# small_mavric.net
KiCad netlist of a schematic drawn in EAGLE
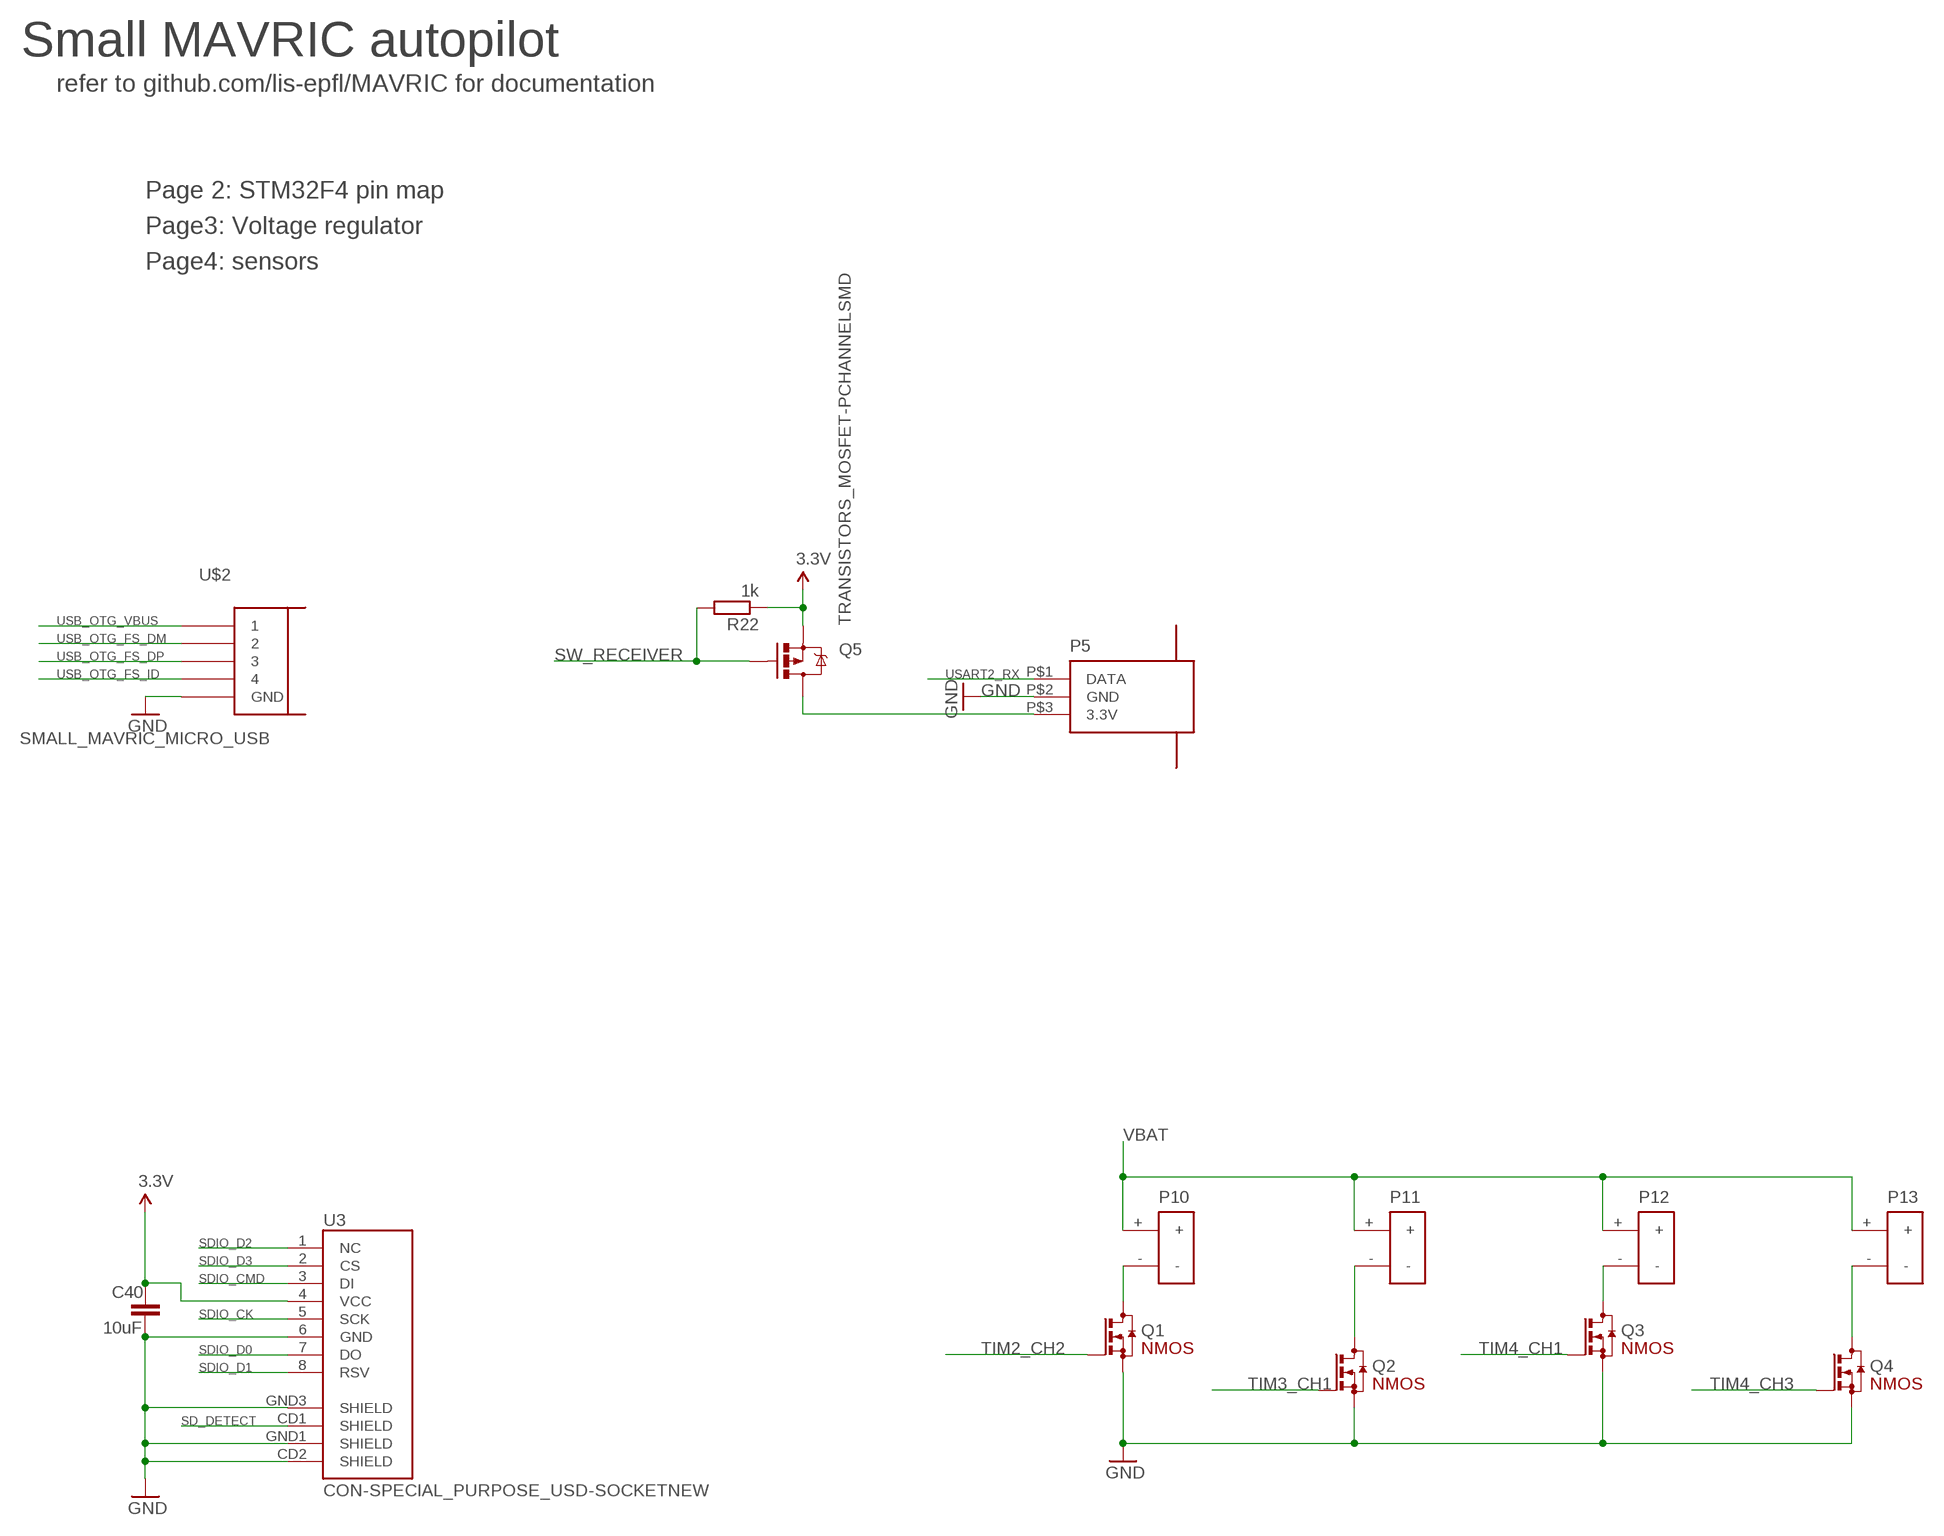
[diagram p0: schematic, sheet 1]
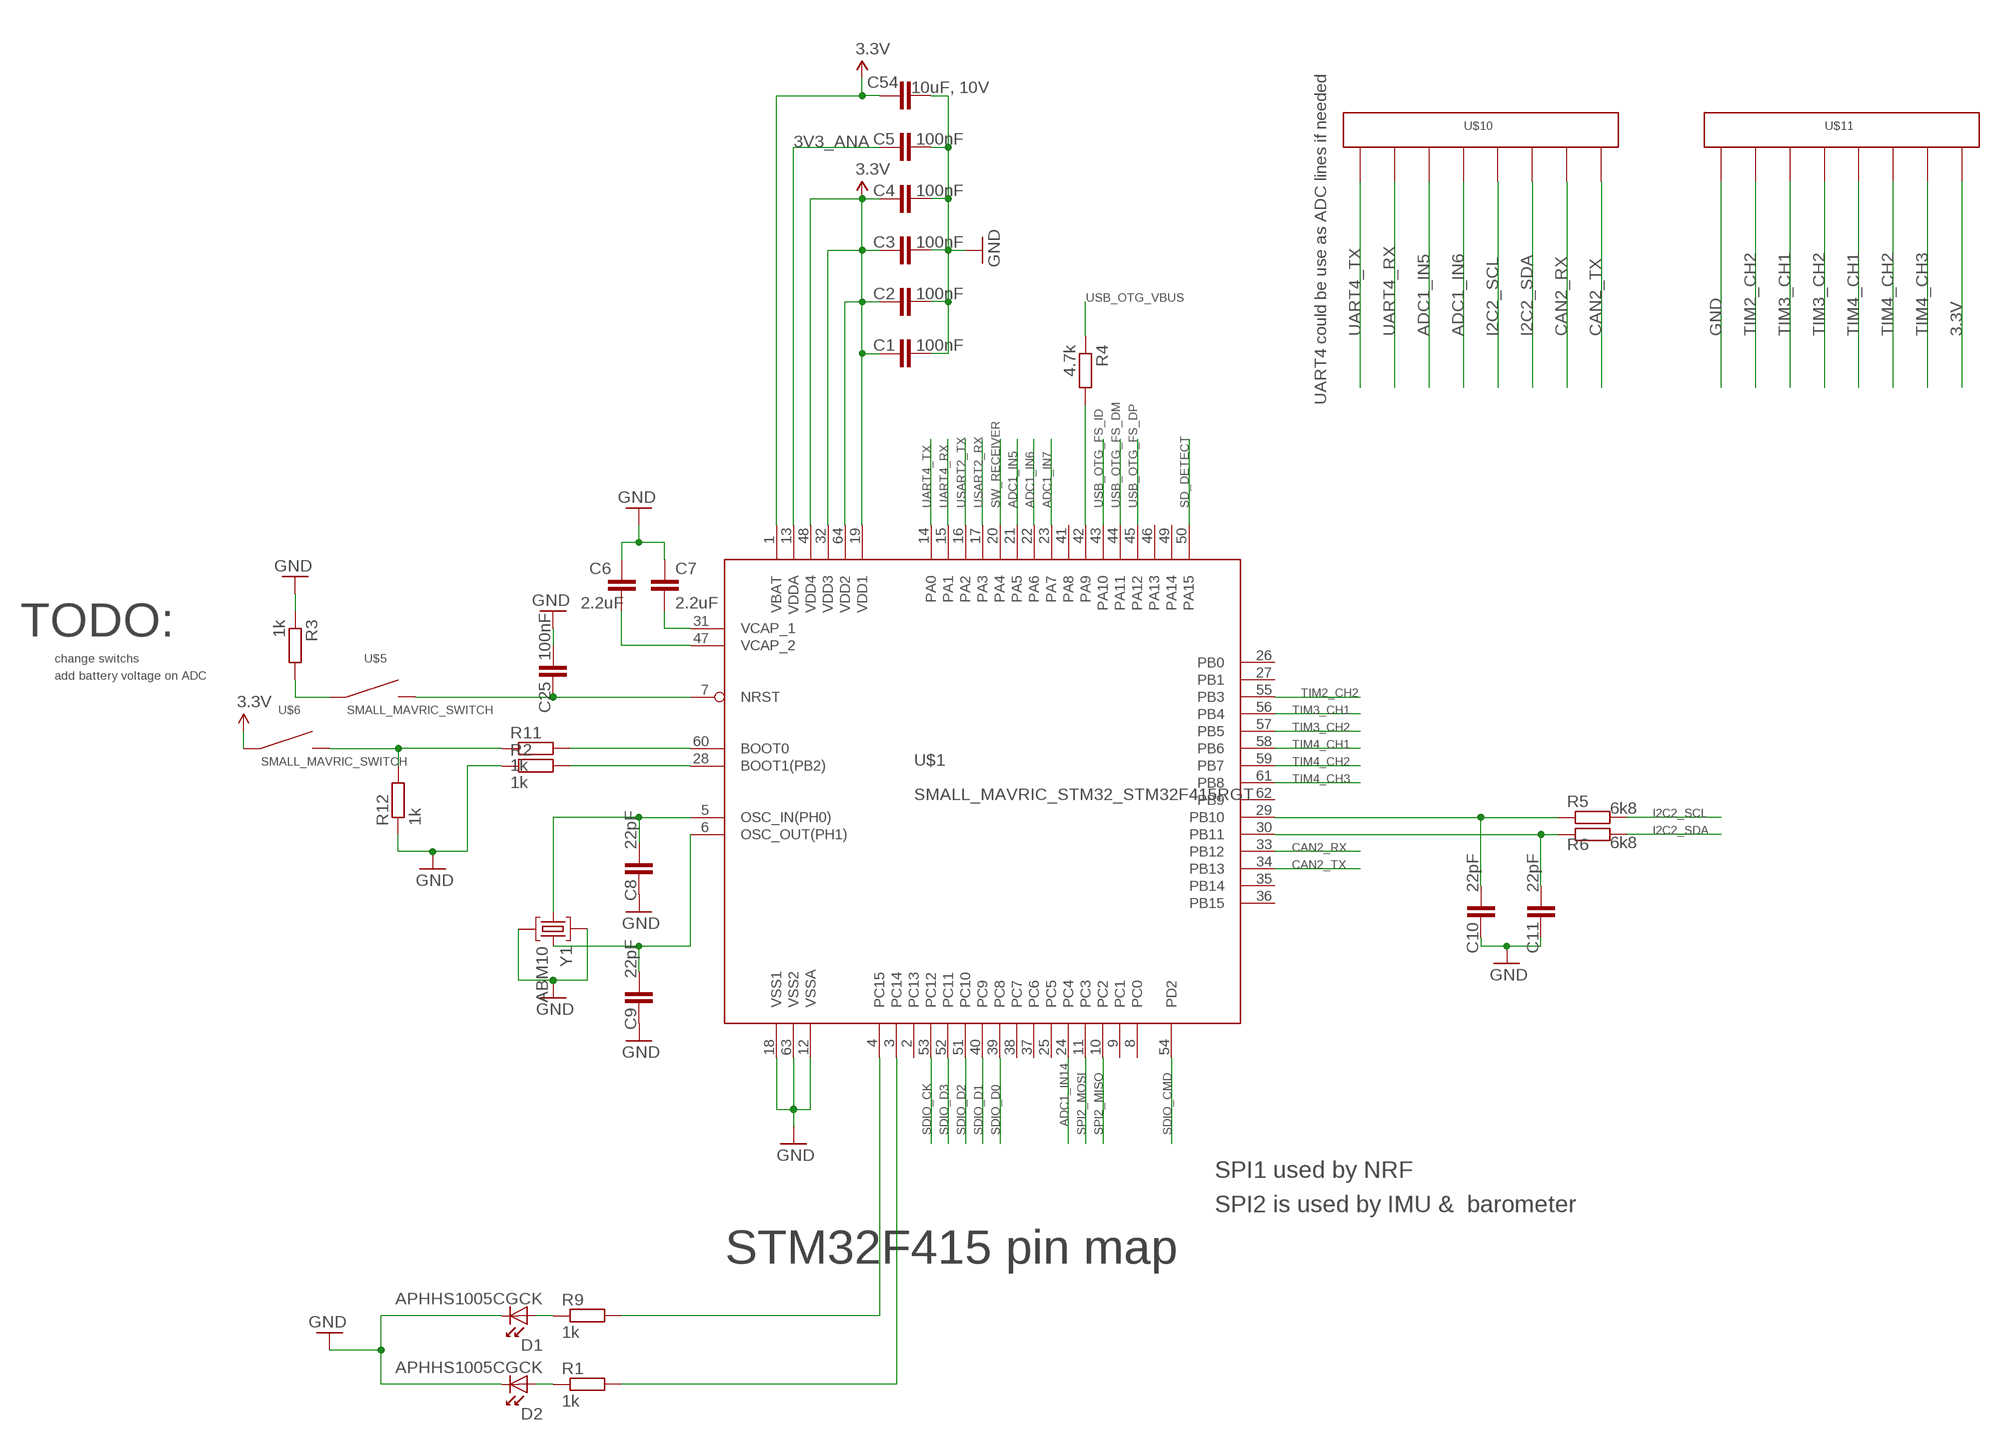
[diagram p1: schematic, sheet 2]
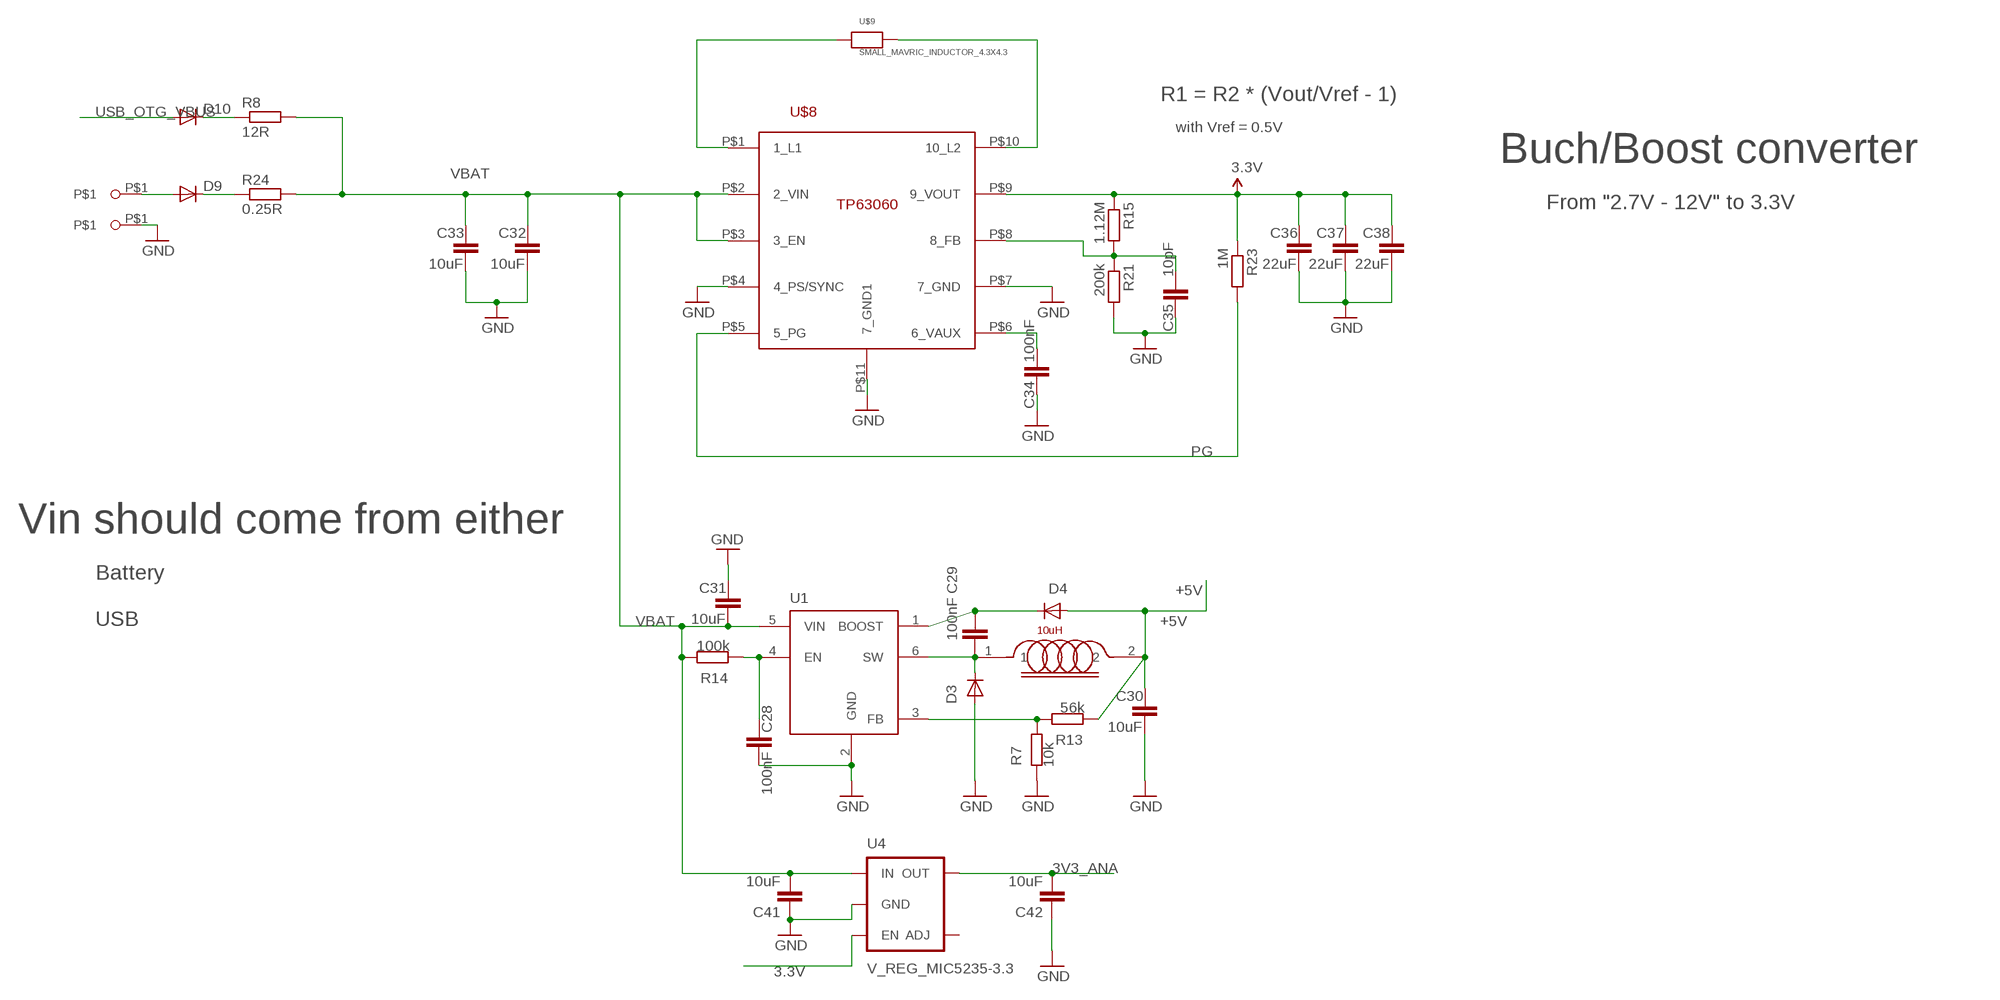
[diagram p2: schematic, sheet 3]
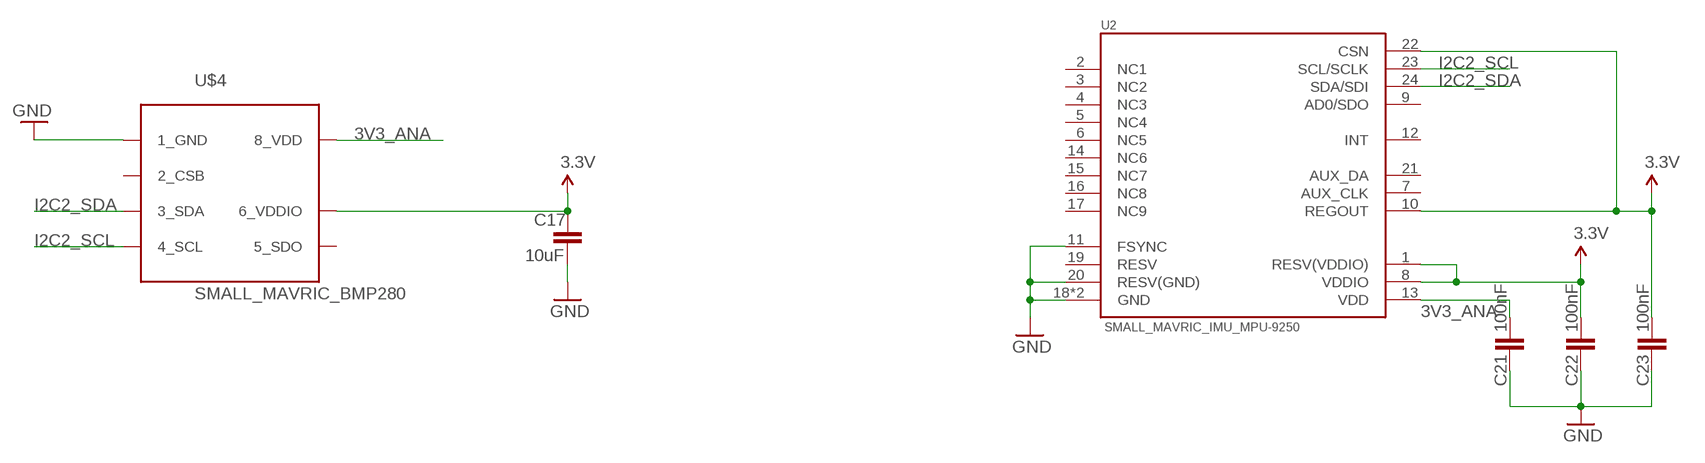
[diagram p3: schematic, sheet 4]

(export (version "E")
  (design (tool "Eeschema 10.0.6"))
  (components
    (comp (ref "C40")
      (value "10uF")
      (footprint "eagle-import:SMALL_MAVRIC_SMALL_MAVRIC_CAPACITOR_C0603")
      (fields (field (name "PLACE_PART") "YES") (field (name "PARTNO") "2.2UF 16V 0603"))
      (libsource (lib "eagle-import") (part "SMALL_MAVRIC_CAPACITOR_C0603"))
    )
    (comp (ref "P5")
      (value "CON-SPECIAL_PURPOSE_SPEKTRUM_RECEIVER")
      (footprint "eagle-import:CON-SPECIAL_PURPOSE_JST_1.5MM_3WAY")
      (fields (field (name "PLACE_PART") "YES"))
      (libsource (lib "eagle-import") (part "CON-SPECIAL_PURPOSE_SPEKTRUM_RECEIVER"))
    )
    (comp (ref "P10")
      (value "POWERSMALL_SMD")
      (footprint "eagle-import:POWER_SMALL_SMD")
      (fields (field (name "PLACE_PART") "NO"))
      (libsource (lib "eagle-import") (part "POWERSMALL_SMD"))
    )
    (comp (ref "P11")
      (value "POWERSMALL_SMD")
      (footprint "eagle-import:POWER_SMALL_SMD")
      (fields (field (name "PLACE_PART") "NO"))
      (libsource (lib "eagle-import") (part "POWERSMALL_SMD"))
    )
    (comp (ref "P12")
      (value "POWERSMALL_SMD")
      (footprint "eagle-import:POWER_SMALL_SMD")
      (fields (field (name "PLACE_PART") "NO"))
      (libsource (lib "eagle-import") (part "POWERSMALL_SMD"))
    )
    (comp (ref "P13")
      (value "POWERSMALL_SMD")
      (footprint "eagle-import:POWER_SMALL_SMD")
      (fields (field (name "PLACE_PART") "NO"))
      (libsource (lib "eagle-import") (part "POWERSMALL_SMD"))
    )
    (comp (ref "Q1")
      (value "N-CHANNEL_SOT23")
      (footprint "eagle-import:SOT23")
      (fields (field (name "PLACE_PART") "YES"))
      (libsource (lib "eagle-import") (part "N-CHANNEL_SOT23"))
    )
    (comp (ref "Q2")
      (value "N-CHANNEL_SOT23")
      (footprint "eagle-import:SOT23")
      (fields (field (name "PLACE_PART") "YES"))
      (libsource (lib "eagle-import") (part "N-CHANNEL_SOT23"))
    )
    (comp (ref "Q3")
      (value "N-CHANNEL_SOT23")
      (footprint "eagle-import:SOT23")
      (fields (field (name "PLACE_PART") "YES"))
      (libsource (lib "eagle-import") (part "N-CHANNEL_SOT23"))
    )
    (comp (ref "Q4")
      (value "N-CHANNEL_SOT23")
      (footprint "eagle-import:SOT23")
      (fields (field (name "PLACE_PART") "YES"))
      (libsource (lib "eagle-import") (part "N-CHANNEL_SOT23"))
    )
    (comp (ref "Q5")
      (value "TRANSISTORS_MOSFET-PCHANNELSMD")
      (footprint "eagle-import:TRANSISTORS_SOT23-3")
      (fields (field (name "PLACE_PART") "YES") (field (name "PLACE_PART_1") "YES"))
      (libsource (lib "eagle-import") (part "TRANSISTORS_MOSFET-PCHANNELSMD"))
    )
    (comp (ref "R22")
      (value "1k")
      (footprint "eagle-import:SMALL_MAVRIC_SMALL_MAVRIC_RESISTOR_R0402")
      (fields (field (name "PLACE_PART") "YES") (field (name "PLACE_PART_1") "YES"))
      (libsource (lib "eagle-import") (part "SMALL_MAVRIC_RESISTOR_R0402"))
    )
    (comp (ref "U$2")
      (value "SMALL_MAVRIC_MICRO_USB")
      (footprint "eagle-import:SMALL_MAVRIC_MICR0_USB")
      (fields (field (name "PLACE_PART") "YES") (field (name "ORDER_CODE") "538-47589-0001"))
      (libsource (lib "eagle-import") (part "SMALL_MAVRIC_MICRO_USB"))
    )
    (comp (ref "U3")
      (value "CON-SPECIAL_PURPOSE_USD-SOCKETNEW")
      (footprint "eagle-import:CON-SPECIAL_PURPOSE_MICRO-SD-SOCKET-PP")
      (fields (field (name "PLACE_PART") "YES"))
      (libsource (lib "eagle-import") (part "CON-SPECIAL_PURPOSE_USD-SOCKETNEW"))
    )
    (comp (ref "C28")
      (value "100nF")
      (footprint "eagle-import:SMALL_MAVRIC_SMALL_MAVRIC_CAPACITOR_C0402")
      (fields (field (name "PLACE_PART") "YES"))
      (libsource (lib "eagle-import") (part "SMALL_MAVRIC_CAPACITOR_C0402"))
    )
    (comp (ref "C29")
      (value "100nF")
      (footprint "eagle-import:SMALL_MAVRIC_SMALL_MAVRIC_CAPACITOR_C0402")
      (fields (field (name "PLACE_PART") "YES"))
      (libsource (lib "eagle-import") (part "SMALL_MAVRIC_CAPACITOR_C0402"))
    )
    (comp (ref "C30")
      (value "10uF")
      (footprint "eagle-import:SMALL_MAVRIC_SMALL_MAVRIC_CAPACITOR_C0603")
      (fields (field (name "PLACE_PART") "YES") (field (name "PARTNO") "2.2UF 16V 0603"))
      (libsource (lib "eagle-import") (part "SMALL_MAVRIC_CAPACITOR_C0603"))
    )
    (comp (ref "C31")
      (value "10uF")
      (footprint "eagle-import:SMALL_MAVRIC_SMALL_MAVRIC_CAPACITOR_C0603")
      (fields (field (name "PLACE_PART") "YES") (field (name "PARTNO") "2.2UF 16V 0603"))
      (libsource (lib "eagle-import") (part "SMALL_MAVRIC_CAPACITOR_C0603"))
    )
    (comp (ref "C32")
      (value "10uF")
      (footprint "eagle-import:SMALL_MAVRIC_SMALL_MAVRIC_CAPACITOR_C0603")
      (fields (field (name "PLACE_PART") "YES") (field (name "PARTNO") "2.2UF 16V 0603"))
      (libsource (lib "eagle-import") (part "SMALL_MAVRIC_CAPACITOR_C0603"))
    )
    (comp (ref "C33")
      (value "10uF")
      (footprint "eagle-import:SMALL_MAVRIC_SMALL_MAVRIC_CAPACITOR_C0603")
      (fields (field (name "PLACE_PART") "YES") (field (name "PARTNO") "2.2UF 16V 0603"))
      (libsource (lib "eagle-import") (part "SMALL_MAVRIC_CAPACITOR_C0603"))
    )
    (comp (ref "C34")
      (value "100nF")
      (footprint "eagle-import:SMALL_MAVRIC_SMALL_MAVRIC_CAPACITOR_C0402")
      (fields (field (name "PLACE_PART") "YES"))
      (libsource (lib "eagle-import") (part "SMALL_MAVRIC_CAPACITOR_C0402"))
    )
    (comp (ref "C35")
      (value "10pF")
      (footprint "eagle-import:SMALL_MAVRIC_SMALL_MAVRIC_CAPACITOR_C0402")
      (fields (field (name "PLACE_PART") "YES"))
      (libsource (lib "eagle-import") (part "SMALL_MAVRIC_CAPACITOR_C0402"))
    )
    (comp (ref "C36")
      (value "22uF")
      (footprint "eagle-import:SMALL_MAVRIC_SMALL_MAVRIC_CAPACITOR_C0603")
      (fields (field (name "PLACE_PART") "YES") (field (name "PARTNO") "2.2UF 16V 0603"))
      (libsource (lib "eagle-import") (part "SMALL_MAVRIC_CAPACITOR_C0603"))
    )
    (comp (ref "C37")
      (value "22uF")
      (footprint "eagle-import:SMALL_MAVRIC_SMALL_MAVRIC_CAPACITOR_C0603")
      (fields (field (name "PLACE_PART") "YES") (field (name "PARTNO") "2.2UF 16V 0603"))
      (libsource (lib "eagle-import") (part "SMALL_MAVRIC_CAPACITOR_C0603"))
    )
    (comp (ref "C38")
      (value "22uF")
      (footprint "eagle-import:SMALL_MAVRIC_SMALL_MAVRIC_CAPACITOR_C0603")
      (fields (field (name "PLACE_PART") "YES") (field (name "PARTNO") "2.2UF 16V 0603"))
      (libsource (lib "eagle-import") (part "SMALL_MAVRIC_CAPACITOR_C0603"))
    )
    (comp (ref "C41")
      (value "10uF")
      (footprint "eagle-import:C0805")
      (fields (field (name "PLACE_PART") "YES"))
      (libsource (lib "eagle-import") (part "C-EUC0805"))
    )
    (comp (ref "C42")
      (value "10uF")
      (footprint "eagle-import:C0805")
      (fields (field (name "PLACE_PART") "YES"))
      (libsource (lib "eagle-import") (part "C-EUC0805"))
    )
    (comp (ref "D3")
      (value "SMALL_MAVRIC_POWER_DIODESOD")
      (footprint "eagle-import:SMALL_MAVRIC_POWER_SOD-323")
      (fields
        (field (name "PLACE_PART") "YES")
        (field (name "DISTRIBUTOR") "Digikey")
        (field (name "ORDER_CODE") "568-4128-1-ND")
      )
      (libsource (lib "eagle-import") (part "SMALL_MAVRIC_POWER_DIODESOD"))
    )
    (comp (ref "D4")
      (value "SMALL_MAVRIC_POWER_DIODESOD")
      (footprint "eagle-import:SMALL_MAVRIC_POWER_SOD-323")
      (fields
        (field (name "PLACE_PART") "YES")
        (field (name "DISTRIBUTOR") "Digikey")
        (field (name "ORDER_CODE") "568-4128-1-ND")
      )
      (libsource (lib "eagle-import") (part "SMALL_MAVRIC_POWER_DIODESOD"))
    )
    (comp (ref "D9")
      (value "SMALL_MAVRIC_POWER_DIODESOD")
      (footprint "eagle-import:SMALL_MAVRIC_POWER_SOD-323")
      (fields
        (field (name "PLACE_PART") "YES")
        (field (name "DISTRIBUTOR") "Digikey")
        (field (name "ORDER_CODE") "568-4128-1-ND")
      )
      (libsource (lib "eagle-import") (part "SMALL_MAVRIC_POWER_DIODESOD"))
    )
    (comp (ref "D10")
      (value "SMALL_MAVRIC_POWER_DIODESOD")
      (footprint "eagle-import:SMALL_MAVRIC_POWER_SOD-323")
      (fields
        (field (name "PLACE_PART") "YES")
        (field (name "DISTRIBUTOR") "Digikey")
        (field (name "ORDER_CODE") "568-4128-1-ND")
        (field (name "PLACE_PART_1") "YES")
      )
      (libsource (lib "eagle-import") (part "SMALL_MAVRIC_POWER_DIODESOD"))
    )
    (comp (ref "L1")
      (value "10uH")
      (footprint "eagle-import:POWER_C1210")
      (fields (field (name "PLACE_PART") "YES"))
      (libsource (lib "eagle-import") (part "POWER_INDUCTOR1210"))
    )
    (comp (ref "R7")
      (value "10k")
      (footprint "eagle-import:SMALL_MAVRIC_SMALL_MAVRIC_RESISTOR_R0402")
      (fields (field (name "PLACE_PART") "YES"))
      (libsource (lib "eagle-import") (part "SMALL_MAVRIC_RESISTOR_R0402"))
    )
    (comp (ref "R8")
      (value "12R")
      (footprint "eagle-import:SMALL_MAVRIC_SMALL_MAVRIC_RESISTOR_R0402")
      (fields (field (name "PLACE_PART") "YES"))
      (libsource (lib "eagle-import") (part "SMALL_MAVRIC_RESISTOR_R0402"))
    )
    (comp (ref "R13")
      (value "56k")
      (footprint "eagle-import:SMALL_MAVRIC_SMALL_MAVRIC_RESISTOR_R0402")
      (fields (field (name "PLACE_PART") "YES"))
      (libsource (lib "eagle-import") (part "SMALL_MAVRIC_RESISTOR_R0402"))
    )
    (comp (ref "R14")
      (value "100k")
      (footprint "eagle-import:SMALL_MAVRIC_SMALL_MAVRIC_RESISTOR_R0402")
      (fields (field (name "PLACE_PART") "YES"))
      (libsource (lib "eagle-import") (part "SMALL_MAVRIC_RESISTOR_R0402"))
    )
    (comp (ref "R15")
      (value "1.12M")
      (footprint "eagle-import:SMALL_MAVRIC_SMALL_MAVRIC_RESISTOR_R0402")
      (fields (field (name "PLACE_PART") "YES"))
      (libsource (lib "eagle-import") (part "SMALL_MAVRIC_RESISTOR_R0402"))
    )
    (comp (ref "R21")
      (value "200k")
      (footprint "eagle-import:SMALL_MAVRIC_SMALL_MAVRIC_RESISTOR_R0402")
      (fields (field (name "PLACE_PART") "YES"))
      (libsource (lib "eagle-import") (part "SMALL_MAVRIC_RESISTOR_R0402"))
    )
    (comp (ref "R23")
      (value "1M")
      (footprint "eagle-import:SMALL_MAVRIC_SMALL_MAVRIC_RESISTOR_R0402")
      (fields (field (name "PLACE_PART") "YES"))
      (libsource (lib "eagle-import") (part "SMALL_MAVRIC_RESISTOR_R0402"))
    )
    (comp (ref "R24")
      (value "0.25R")
      (footprint "eagle-import:SMALL_MAVRIC_SMALL_MAVRIC_RESISTOR_R0402")
      (fields (field (name "PLACE_PART") "YES"))
      (libsource (lib "eagle-import") (part "SMALL_MAVRIC_RESISTOR_R0402"))
    )
    (comp (ref "U$8")
      (value "SMALL_MAVRIC_POWER_TPS63060")
      (footprint "eagle-import:SMALL_MAVRIC_POWER_PWSON")
      (fields (field (name "PLACE_PART") "YES"))
      (libsource (lib "eagle-import") (part "SMALL_MAVRIC_POWER_TPS63060"))
    )
    (comp (ref "U$9")
      (value "SMALL_MAVRIC_INDUCTOR_4.3X4.3")
      (footprint "eagle-import:SMALL_MAVRIC_SMALL_MAVRIC_SMALL_MAVRIC_INDUCTOR_4.3X4.3")
      (fields
        (field (name "PLACE_PART") "YES")
        (field (name "DISTRIBUTOR") "mouser")
        (field (name "ORDER_CODE") "994-XFL4020-102MEC")
      )
      (libsource (lib "eagle-import") (part "SMALL_MAVRIC_INDUCTOR_4.3X4.3"))
    )
    (comp (ref "U$15")
      (value "SMALL_MAVRIC_SMALL_CONNECTOR")
      (footprint "eagle-import:SMALL_MAVRIC_SMALL_CONN")
      (fields
        (field (name "PLACE_PART") "YES")
        (field (name "DISTRIBUTOR") "Mouser")
        (field (name "PLACE_PART_1") "YES")
      )
      (libsource (lib "eagle-import") (part "SMALL_MAVRIC_SMALL_CONNECTOR"))
    )
    (comp (ref "U$16")
      (value "SMALL_MAVRIC_SMALL_CONNECTOR")
      (footprint "eagle-import:SMALL_MAVRIC_SMALL_CONN")
      (fields
        (field (name "PLACE_PART") "YES")
        (field (name "DISTRIBUTOR") "Mouser")
        (field (name "PLACE_PART_1") "YES")
      )
      (libsource (lib "eagle-import") (part "SMALL_MAVRIC_SMALL_CONNECTOR"))
    )
    (comp (ref "U1")
      (value "POWER_LM2734")
      (footprint "eagle-import:POWER_SOT23-6")
      (fields (field (name "PLACE_PART") "YES"))
      (libsource (lib "eagle-import") (part "POWER_LM2734"))
    )
    (comp (ref "U4")
      (value "V_REG_MIC5235-3.3")
      (footprint "eagle-import:SOT23-5")
      (fields (field (name "PLACE_PART") "YES"))
      (libsource (lib "eagle-import") (part "V_REG_MIC5235"))
    )
    (comp (ref "C1")
      (value "100nF")
      (footprint "eagle-import:SMALL_MAVRIC_SMALL_MAVRIC_CAPACITOR_C0402")
      (fields (field (name "PLACE_PART") "YES"))
      (libsource (lib "eagle-import") (part "SMALL_MAVRIC_CAPACITOR_C0402"))
    )
    (comp (ref "C2")
      (value "100nF")
      (footprint "eagle-import:SMALL_MAVRIC_SMALL_MAVRIC_CAPACITOR_C0402")
      (fields (field (name "PLACE_PART") "YES"))
      (libsource (lib "eagle-import") (part "SMALL_MAVRIC_CAPACITOR_C0402"))
    )
    (comp (ref "C3")
      (value "100nF")
      (footprint "eagle-import:SMALL_MAVRIC_SMALL_MAVRIC_CAPACITOR_C0402")
      (fields (field (name "PLACE_PART") "YES"))
      (libsource (lib "eagle-import") (part "SMALL_MAVRIC_CAPACITOR_C0402"))
    )
    (comp (ref "C4")
      (value "100nF")
      (footprint "eagle-import:SMALL_MAVRIC_SMALL_MAVRIC_CAPACITOR_C0402")
      (fields (field (name "PLACE_PART") "YES"))
      (libsource (lib "eagle-import") (part "SMALL_MAVRIC_CAPACITOR_C0402"))
    )
    (comp (ref "C5")
      (value "100nF")
      (footprint "eagle-import:SMALL_MAVRIC_SMALL_MAVRIC_CAPACITOR_C0402")
      (fields (field (name "PLACE_PART") "YES"))
      (libsource (lib "eagle-import") (part "SMALL_MAVRIC_CAPACITOR_C0402"))
    )
    (comp (ref "C6")
      (value "2.2uF")
      (footprint "eagle-import:SMALL_MAVRIC_SMALL_MAVRIC_CAPACITOR_C0603")
      (fields (field (name "PLACE_PART") "YES") (field (name "PARTNO") "2.2UF 16V 0603"))
      (libsource (lib "eagle-import") (part "SMALL_MAVRIC_CAPACITOR_C0603"))
    )
    (comp (ref "C7")
      (value "2.2uF")
      (footprint "eagle-import:SMALL_MAVRIC_SMALL_MAVRIC_CAPACITOR_C0603")
      (fields (field (name "PLACE_PART") "YES") (field (name "PARTNO") "2.2UF 16V 0603"))
      (libsource (lib "eagle-import") (part "SMALL_MAVRIC_CAPACITOR_C0603"))
    )
    (comp (ref "C8")
      (value "22pF")
      (footprint "eagle-import:SMALL_MAVRIC_SMALL_MAVRIC_CAPACITOR_C0402")
      (fields (field (name "PLACE_PART") "YES"))
      (libsource (lib "eagle-import") (part "SMALL_MAVRIC_CAPACITOR_C0402"))
    )
    (comp (ref "C9")
      (value "22pF")
      (footprint "eagle-import:SMALL_MAVRIC_SMALL_MAVRIC_CAPACITOR_C0402")
      (fields (field (name "PLACE_PART") "YES"))
      (libsource (lib "eagle-import") (part "SMALL_MAVRIC_CAPACITOR_C0402"))
    )
    (comp (ref "C10")
      (value "22pF")
      (footprint "eagle-import:SMALL_MAVRIC_SMALL_MAVRIC_CAPACITOR_C0402")
      (fields (field (name "PLACE_PART") "YES"))
      (libsource (lib "eagle-import") (part "SMALL_MAVRIC_CAPACITOR_C0402"))
    )
    (comp (ref "C11")
      (value "22pF")
      (footprint "eagle-import:SMALL_MAVRIC_SMALL_MAVRIC_CAPACITOR_C0402")
      (fields (field (name "PLACE_PART") "YES"))
      (libsource (lib "eagle-import") (part "SMALL_MAVRIC_CAPACITOR_C0402"))
    )
    (comp (ref "C25")
      (value "100nF")
      (footprint "eagle-import:SMALL_MAVRIC_SMALL_MAVRIC_CAPACITOR_C0402")
      (fields (field (name "PLACE_PART") "YES"))
      (libsource (lib "eagle-import") (part "SMALL_MAVRIC_CAPACITOR_C0402"))
    )
    (comp (ref "C54")
      (value "10uF, 10V")
      (footprint "eagle-import:SMALL_MAVRIC_SMALL_MAVRIC_CAPACITOR_C0603")
      (fields (field (name "PLACE_PART") "YES") (field (name "PARTNO") "10UF 10V 0805"))
      (libsource (lib "eagle-import") (part "SMALL_MAVRIC_CAPACITOR_C0603"))
    )
    (comp (ref "D1")
      (value "APHHS1005CGCK")
      (footprint "eagle-import:LED_0402")
      (libsource (lib "eagle-import") (part "COMMON_LED"))
    )
    (comp (ref "D2")
      (value "APHHS1005CGCK")
      (footprint "eagle-import:LED_0402")
      (libsource (lib "eagle-import") (part "COMMON_LED"))
    )
    (comp (ref "R1")
      (value "1k")
      (footprint "eagle-import:SMALL_MAVRIC_SMALL_MAVRIC_RESISTOR_R0402")
      (fields (field (name "PLACE_PART") "YES"))
      (libsource (lib "eagle-import") (part "SMALL_MAVRIC_RESISTOR_R0402"))
    )
    (comp (ref "R2")
      (value "1k")
      (footprint "eagle-import:SMALL_MAVRIC_SMALL_MAVRIC_RESISTOR_R0402")
      (fields (field (name "PLACE_PART") "YES"))
      (libsource (lib "eagle-import") (part "SMALL_MAVRIC_RESISTOR_R0402"))
    )
    (comp (ref "R3")
      (value "1k")
      (footprint "eagle-import:SMALL_MAVRIC_SMALL_MAVRIC_RESISTOR_R0402")
      (fields (field (name "PLACE_PART") "YES"))
      (libsource (lib "eagle-import") (part "SMALL_MAVRIC_RESISTOR_R0402"))
    )
    (comp (ref "R4")
      (value "4.7k")
      (footprint "eagle-import:SMALL_MAVRIC_SMALL_MAVRIC_RESISTOR_R0402")
      (fields (field (name "PLACE_PART") "YES"))
      (libsource (lib "eagle-import") (part "SMALL_MAVRIC_RESISTOR_R0402"))
    )
    (comp (ref "R5")
      (value "6k8")
      (footprint "eagle-import:SMALL_MAVRIC_SMALL_MAVRIC_RESISTOR_R0402")
      (fields (field (name "PLACE_PART") "YES"))
      (libsource (lib "eagle-import") (part "SMALL_MAVRIC_RESISTOR_R0402"))
    )
    (comp (ref "R6")
      (value "6k8")
      (footprint "eagle-import:SMALL_MAVRIC_SMALL_MAVRIC_RESISTOR_R0402")
      (fields (field (name "PLACE_PART") "YES"))
      (libsource (lib "eagle-import") (part "SMALL_MAVRIC_RESISTOR_R0402"))
    )
    (comp (ref "R9")
      (value "1k")
      (footprint "eagle-import:SMALL_MAVRIC_SMALL_MAVRIC_RESISTOR_R0402")
      (fields (field (name "PLACE_PART") "YES"))
      (libsource (lib "eagle-import") (part "SMALL_MAVRIC_RESISTOR_R0402"))
    )
    (comp (ref "R11")
      (value "1k")
      (footprint "eagle-import:SMALL_MAVRIC_SMALL_MAVRIC_RESISTOR_R0402")
      (fields (field (name "PLACE_PART") "YES"))
      (libsource (lib "eagle-import") (part "SMALL_MAVRIC_RESISTOR_R0402"))
    )
    (comp (ref "R12")
      (value "1k")
      (footprint "eagle-import:SMALL_MAVRIC_SMALL_MAVRIC_RESISTOR_R0402")
      (fields (field (name "PLACE_PART") "YES"))
      (libsource (lib "eagle-import") (part "SMALL_MAVRIC_RESISTOR_R0402"))
    )
    (comp (ref "U$1")
      (value "SMALL_MAVRIC_STM32_STM32F415RGT")
      (footprint "eagle-import:SMALL_MAVRIC_STM32_LQFP64")
      (fields (field (name "PLACE_PART") "YES"))
      (libsource (lib "eagle-import") (part "SMALL_MAVRIC_STM32_STM32F415RGT"))
    )
    (comp (ref "U$5")
      (value "SMALL_MAVRIC_SWITCH")
      (footprint "eagle-import:SMALL_MAVRIC_SWITCH")
      (fields
        (field (name "PLACE_PART") "YES")
        (field (name "DISTRIBUTOR") "digikey")
        (field (name "ORDER_CODE") "SW1022CT-ND")
      )
      (libsource (lib "eagle-import") (part "SMALL_MAVRIC_SWITCH"))
    )
    (comp (ref "U$6")
      (value "SMALL_MAVRIC_SWITCH")
      (footprint "eagle-import:SMALL_MAVRIC_SWITCH")
      (fields
        (field (name "PLACE_PART") "YES")
        (field (name "DISTRIBUTOR") "digikey")
        (field (name "ORDER_CODE") "SW1022CT-ND")
      )
      (libsource (lib "eagle-import") (part "SMALL_MAVRIC_SWITCH"))
    )
    (comp (ref "U$10")
      (value "SMALL_MAVRIC_CONN_RAIL_X8")
      (footprint "eagle-import:SMALL_MAVRIC_CONN_RAIL_X8")
      (libsource (lib "eagle-import") (part "SMALL_MAVRIC_CONN_RAIL_X8"))
    )
    (comp (ref "U$11")
      (value "SMALL_MAVRIC_CONN_RAIL_X8")
      (footprint "eagle-import:SMALL_MAVRIC_CONN_RAIL_X8")
      (libsource (lib "eagle-import") (part "SMALL_MAVRIC_CONN_RAIL_X8"))
    )
    (comp (ref "Y1")
      (value "ABM10")
      (footprint "eagle-import:OSCILLATOR_ABM10")
      (fields (field (name "PARTNO") "ABM10 25MHz"))
      (libsource (lib "eagle-import") (part "ABM10"))
    )
    (comp (ref "C17")
      (value "10uF")
      (footprint "eagle-import:SMALL_MAVRIC_SMALL_MAVRIC_CAPACITOR_C0603")
      (fields (field (name "PLACE_PART") "YES") (field (name "PARTNO") "2.2UF 16V 0603"))
      (libsource (lib "eagle-import") (part "SMALL_MAVRIC_CAPACITOR_C0603"))
    )
    (comp (ref "C21")
      (value "100nF")
      (footprint "eagle-import:SMALL_MAVRIC_SMALL_MAVRIC_CAPACITOR_C0402")
      (fields (field (name "PLACE_PART") "YES"))
      (libsource (lib "eagle-import") (part "SMALL_MAVRIC_CAPACITOR_C0402"))
    )
    (comp (ref "C22")
      (value "100nF")
      (footprint "eagle-import:SMALL_MAVRIC_SMALL_MAVRIC_CAPACITOR_C0402")
      (fields (field (name "PLACE_PART") "YES"))
      (libsource (lib "eagle-import") (part "SMALL_MAVRIC_CAPACITOR_C0402"))
    )
    (comp (ref "C23")
      (value "100nF")
      (footprint "eagle-import:SMALL_MAVRIC_SMALL_MAVRIC_CAPACITOR_C0402")
      (fields (field (name "PLACE_PART") "YES"))
      (libsource (lib "eagle-import") (part "SMALL_MAVRIC_CAPACITOR_C0402"))
    )
    (comp (ref "U$4")
      (value "SMALL_MAVRIC_BMP280")
      (footprint "eagle-import:SMALL_MAVRIC_SMALL_MAVRIC_SMALL_MAVRIC_LGA-8")
      (fields
        (field (name "PLACE_PART") "YES")
        (field (name "DISTRIBUTOR") "mouser")
        (field (name "ORDER_CODE") "262-BMP280")
      )
      (libsource (lib "eagle-import") (part "SMALL_MAVRIC_BMP280"))
    )
    (comp (ref "U2")
      (value "SMALL_MAVRIC_IMU_MPU-9250")
      (footprint "eagle-import:SMALL_MAVRIC_SMALL_MAVRIC_QFN-24_3.0X3.0MM")
      (fields
        (field (name "PLACE_PART") "YES")
        (field (name "DISTRIBUTOR") "digikey")
        (field (name "ORDER_CODE") "1428-1019-1-ND")
      )
      (libsource (lib "eagle-import") (part "SMALL_MAVRIC_IMU_MPU-9250"))
    )
  )
  (nets
    (net (code "1") (name "+5V") (class "Default")
      (node (ref "C30") (pin "1") (pinfunction "1_1") (pintype "passive"))
      (node (ref "D4") (pin "2") (pinfunction "A_2") (pintype "passive"))
      (node (ref "L1") (pin "2") (pinfunction "2_2") (pintype "bidirectional"))
      (node (ref "R13") (pin "1") (pinfunction "1_1") (pintype "passive"))
    )
    (net (code "2") (name "3.3V") (class "Default")
      (node (ref "C1") (pin "1") (pinfunction "1_1") (pintype "passive"))
      (node (ref "C17") (pin "1") (pinfunction "1_1") (pintype "passive"))
      (node (ref "C2") (pin "1") (pinfunction "1_1") (pintype "passive"))
      (node (ref "C22") (pin "2") (pinfunction "2_2") (pintype "passive"))
      (node (ref "C23") (pin "2") (pinfunction "2_2") (pintype "passive"))
      (node (ref "C3") (pin "1") (pinfunction "1_1") (pintype "passive"))
      (node (ref "C36") (pin "1") (pinfunction "1_1") (pintype "passive"))
      (node (ref "C37") (pin "1") (pinfunction "1_1") (pintype "passive"))
      (node (ref "C38") (pin "1") (pinfunction "1_1") (pintype "passive"))
      (node (ref "C4") (pin "1") (pinfunction "1_1") (pintype "passive"))
      (node (ref "C40") (pin "1") (pinfunction "1_1") (pintype "passive"))
      (node (ref "C54") (pin "1") (pinfunction "1_1") (pintype "passive"))
      (node (ref "Q5") (pin "2") (pinfunction "S_2") (pintype "passive"))
      (node (ref "R15") (pin "1") (pinfunction "1_1") (pintype "passive"))
      (node (ref "R22") (pin "1") (pinfunction "1_1") (pintype "passive"))
      (node (ref "R23") (pin "1") (pinfunction "1_1") (pintype "passive"))
      (node (ref "U$1") (pin "1") (pinfunction "VBAT_1") (pintype "power_in"))
      (node (ref "U$1") (pin "19") (pinfunction "VDD1_19") (pintype "power_in"))
      (node (ref "U$1") (pin "32") (pinfunction "VDD3_32") (pintype "power_in"))
      (node (ref "U$1") (pin "48") (pinfunction "VDD4_48") (pintype "power_in"))
      (node (ref "U$1") (pin "64") (pinfunction "VDD2_64") (pintype "power_in"))
      (node (ref "U$11") (pin "P$8") (pinfunction "P$8_P$8") (pintype "bidirectional"))
      (node (ref "U$4") (pin "P$6") (pinfunction "6_VDDIO_P$6") (pintype "bidirectional"))
      (node (ref "U$6") (pin "1") (pinfunction "P$1_1") (pintype "bidirectional"))
      (node (ref "U$8") (pin "P$9") (pinfunction "9_VOUT_P$9") (pintype "bidirectional"))
      (node (ref "U2") (pin "1") (pinfunction "RESV(VDDIO)_1") (pintype "passive"))
      (node (ref "U2") (pin "10") (pinfunction "REGOUT_10") (pintype "passive"))
      (node (ref "U2") (pin "22") (pinfunction "CSN_22") (pintype "input"))
      (node (ref "U2") (pin "8") (pinfunction "VDDIO_8") (pintype "power_in"))
      (node (ref "U3") (pin "4") (pinfunction "VCC_4") (pintype "bidirectional"))
      (node (ref "U4") (pin "3") (pinfunction "EN_3") (pintype "input"))
    )
    (net (code "3") (name "3V3_ANA") (class "Default")
      (node (ref "C21") (pin "2") (pinfunction "2_2") (pintype "passive"))
      (node (ref "C42") (pin "2") (pinfunction "2_2") (pintype "passive"))
      (node (ref "C5") (pin "1") (pinfunction "1_1") (pintype "passive"))
      (node (ref "U$1") (pin "13") (pinfunction "VDDA_13") (pintype "power_in"))
      (node (ref "U$4") (pin "P$8") (pinfunction "8_VDD_P$8") (pintype "bidirectional"))
      (node (ref "U2") (pin "13") (pinfunction "VDD_13") (pintype "power_in"))
      (node (ref "U4") (pin "5") (pinfunction "OUT_5") (pintype "passive"))
    )
    (net (code "4") (name "ADC1_IN5") (class "Default")
      (node (ref "U$1") (pin "21") (pinfunction "PA5_21") (pintype "bidirectional"))
      (node (ref "U$10") (pin "P$3") (pinfunction "P$3_P$3") (pintype "bidirectional"))
    )
    (net (code "5") (name "ADC1_IN6") (class "Default")
      (node (ref "U$1") (pin "22") (pinfunction "PA6_22") (pintype "bidirectional"))
      (node (ref "U$10") (pin "P$4") (pinfunction "P$4_P$4") (pintype "bidirectional"))
    )
    (net (code "6") (name "ADC1_IN7") (class "Default")
      (node (ref "U$1") (pin "23") (pinfunction "PA7_23") (pintype "bidirectional"))
    )
    (net (code "7") (name "ADC1_IN14") (class "Default")
      (node (ref "U$1") (pin "24") (pinfunction "PC4_24") (pintype "bidirectional"))
    )
    (net (code "8") (name "CAN2_RX") (class "Default")
      (node (ref "U$1") (pin "33") (pinfunction "PB12_33") (pintype "bidirectional"))
      (node (ref "U$10") (pin "P$7") (pinfunction "P$7_P$7") (pintype "bidirectional"))
    )
    (net (code "9") (name "CAN2_TX") (class "Default")
      (node (ref "U$1") (pin "34") (pinfunction "PB13_34") (pintype "bidirectional"))
      (node (ref "U$10") (pin "P$8") (pinfunction "P$8_P$8") (pintype "bidirectional"))
    )
    (net (code "10") (name "GND") (class "Default")
      (node (ref "C1") (pin "2") (pinfunction "2_2") (pintype "passive"))
      (node (ref "C10") (pin "1") (pinfunction "1_1") (pintype "passive"))
      (node (ref "C11") (pin "1") (pinfunction "1_1") (pintype "passive"))
      (node (ref "C17") (pin "2") (pinfunction "2_2") (pintype "passive"))
      (node (ref "C2") (pin "2") (pinfunction "2_2") (pintype "passive"))
      (node (ref "C21") (pin "1") (pinfunction "1_1") (pintype "passive"))
      (node (ref "C22") (pin "1") (pinfunction "1_1") (pintype "passive"))
      (node (ref "C23") (pin "1") (pinfunction "1_1") (pintype "passive"))
      (node (ref "C25") (pin "2") (pinfunction "2_2") (pintype "passive"))
      (node (ref "C28") (pin "2") (pinfunction "2_2") (pintype "passive"))
      (node (ref "C3") (pin "2") (pinfunction "2_2") (pintype "passive"))
      (node (ref "C30") (pin "2") (pinfunction "2_2") (pintype "passive"))
      (node (ref "C31") (pin "1") (pinfunction "1_1") (pintype "passive"))
      (node (ref "C32") (pin "2") (pinfunction "2_2") (pintype "passive"))
      (node (ref "C33") (pin "2") (pinfunction "2_2") (pintype "passive"))
      (node (ref "C34") (pin "1") (pinfunction "1_1") (pintype "passive"))
      (node (ref "C35") (pin "1") (pinfunction "1_1") (pintype "passive"))
      (node (ref "C36") (pin "2") (pinfunction "2_2") (pintype "passive"))
      (node (ref "C37") (pin "2") (pinfunction "2_2") (pintype "passive"))
      (node (ref "C38") (pin "2") (pinfunction "2_2") (pintype "passive"))
      (node (ref "C4") (pin "2") (pinfunction "2_2") (pintype "passive"))
      (node (ref "C40") (pin "2") (pinfunction "2_2") (pintype "passive"))
      (node (ref "C41") (pin "1") (pinfunction "1_1") (pintype "passive"))
      (node (ref "C42") (pin "1") (pinfunction "1_1") (pintype "passive"))
      (node (ref "C5") (pin "2") (pinfunction "2_2") (pintype "passive"))
      (node (ref "C54") (pin "2") (pinfunction "2_2") (pintype "passive"))
      (node (ref "C6") (pin "1") (pinfunction "1_1") (pintype "passive"))
      (node (ref "C7") (pin "1") (pinfunction "1_1") (pintype "passive"))
      (node (ref "C8") (pin "1") (pinfunction "1_1") (pintype "passive"))
      (node (ref "C9") (pin "1") (pinfunction "1_1") (pintype "passive"))
      (node (ref "D1") (pin "C") (pinfunction "C_C") (pintype "passive"))
      (node (ref "D2") (pin "C") (pinfunction "C_C") (pintype "passive"))
      (node (ref "D3") (pin "2") (pinfunction "A_2") (pintype "passive"))
      (node (ref "P5") (pin "P$2") (pinfunction "GND_P$2") (pintype "bidirectional"))
      (node (ref "Q1") (pin "2") (pinfunction "S_2") (pintype "passive"))
      (node (ref "Q2") (pin "2") (pinfunction "S_2") (pintype "passive"))
      (node (ref "Q3") (pin "2") (pinfunction "S_2") (pintype "passive"))
      (node (ref "Q4") (pin "2") (pinfunction "S_2") (pintype "passive"))
      (node (ref "R12") (pin "1") (pinfunction "1_1") (pintype "passive"))
      (node (ref "R2") (pin "1") (pinfunction "1_1") (pintype "passive"))
      (node (ref "R21") (pin "2") (pinfunction "2_2") (pintype "passive"))
      (node (ref "R3") (pin "1") (pinfunction "1_1") (pintype "passive"))
      (node (ref "R7") (pin "1") (pinfunction "1_1") (pintype "passive"))
      (node (ref "U$1") (pin "12") (pinfunction "VSSA_12") (pintype "power_in"))
      (node (ref "U$1") (pin "18") (pinfunction "VSS1_18") (pintype "power_in"))
      (node (ref "U$1") (pin "63") (pinfunction "VSS2_63") (pintype "power_in"))
      (node (ref "U$11") (pin "P$1") (pinfunction "P$1_P$1") (pintype "bidirectional"))
      (node (ref "U$15") (pin "P$1") (pinfunction "P$1_P$1") (pintype "bidirectional"))
      (node (ref "U$2") (pin "5") (pinfunction "GND_5") (pintype "passive"))
      (node (ref "U$4") (pin "P$1") (pinfunction "1_GND_P$1") (pintype "bidirectional"))
      (node (ref "U$4") (pin "P$7") (pinfunction "1_GND_P$7") (pintype "bidirectional"))
      (node (ref "U$8") (pin "P$11") (pinfunction "7_GND1_P$11") (pintype "bidirectional"))
      (node (ref "U$8") (pin "P$4") (pinfunction "4_PS/SYNC_P$4") (pintype "bidirectional"))
      (node (ref "U$8") (pin "P$7") (pinfunction "7_GND_P$7") (pintype "bidirectional"))
      (node (ref "U1") (pin "2") (pinfunction "GND_2") (pintype "bidirectional"))
      (node (ref "U2") (pin "11") (pinfunction "FSYNC_11") (pintype "bidirectional"))
      (node (ref "U2") (pin "18") (pinfunction "GND_18") (pintype "power_in"))
      (node (ref "U2") (pin "20") (pinfunction "RESV(GND)_20") (pintype "passive"))
      (node (ref "U2") (pin "CENTRAL_PAD") (pinfunction "GND_CENTRAL_PAD") (pintype "power_in"))
      (node (ref "U3") (pin "6") (pinfunction "GND_6") (pintype "bidirectional"))
      (node (ref "U3") (pin "CD2") (pinfunction "SHIELD_CD2") (pintype "bidirectional"))
      (node (ref "U3") (pin "GND1") (pinfunction "SHIELD_GND1") (pintype "bidirectional"))
      (node (ref "U3") (pin "GND3") (pinfunction "SHIELD_GND3") (pintype "bidirectional"))
      (node (ref "U4") (pin "2") (pinfunction "GND_2") (pintype "input"))
      (node (ref "Y1") (pin "2") (pinfunction "2_2") (pintype "passive"))
      (node (ref "Y1") (pin "4") (pinfunction "4_4") (pintype "passive"))
    )
    (net (code "11") (name "I2C2_SCL") (class "Default")
      (node (ref "R5") (pin "2") (pinfunction "2_2") (pintype "passive"))
      (node (ref "U$10") (pin "P$5") (pinfunction "P$5_P$5") (pintype "bidirectional"))
      (node (ref "U$4") (pin "P$4") (pinfunction "4_SCL_P$4") (pintype "bidirectional"))
      (node (ref "U2") (pin "23") (pinfunction "SCL/SCLK_23") (pintype "input"))
    )
    (net (code "12") (name "I2C2_SDA") (class "Default")
      (node (ref "R6") (pin "2") (pinfunction "2_2") (pintype "passive"))
      (node (ref "U$10") (pin "P$6") (pinfunction "P$6_P$6") (pintype "bidirectional"))
      (node (ref "U$4") (pin "P$3") (pinfunction "3_SDA_P$3") (pintype "bidirectional"))
      (node (ref "U2") (pin "24") (pinfunction "SDA/SDI_24") (pintype "input"))
    )
    (net (code "13") (name "Net-(D1-PadA)") (class "Default")
      (node (ref "D1") (pin "A") (pinfunction "A_A") (pintype "passive"))
      (node (ref "R9") (pin "1") (pinfunction "1_1") (pintype "passive"))
    )
    (net (code "14") (name "Net-(D2-PadA)") (class "Default")
      (node (ref "D2") (pin "A") (pinfunction "A_A") (pintype "passive"))
      (node (ref "R1") (pin "1") (pinfunction "1_1") (pintype "passive"))
    )
    (net (code "15") (name "Net-(D3-C)") (class "Default")
      (node (ref "C29") (pin "2") (pinfunction "2_2") (pintype "passive"))
      (node (ref "D3") (pin "1") (pinfunction "C_1") (pintype "passive"))
      (node (ref "L1") (pin "1") (pinfunction "1_1") (pintype "bidirectional"))
      (node (ref "U1") (pin "6") (pinfunction "SW_6") (pintype "bidirectional"))
    )
    (net (code "16") (name "Net-(D4-C)") (class "Default")
      (node (ref "C29") (pin "1") (pinfunction "1_1") (pintype "passive"))
      (node (ref "D4") (pin "1") (pinfunction "C_1") (pintype "passive"))
      (node (ref "U1") (pin "1") (pinfunction "BOOST_1") (pintype "bidirectional"))
    )
    (net (code "17") (name "Net-(D9-A)") (class "Default")
      (node (ref "D9") (pin "2") (pinfunction "A_2") (pintype "passive"))
      (node (ref "U$16") (pin "P$1") (pinfunction "P$1_P$1") (pintype "bidirectional"))
    )
    (net (code "18") (name "Net-(D9-C)") (class "Default")
      (node (ref "D9") (pin "1") (pinfunction "C_1") (pintype "passive"))
      (node (ref "R24") (pin "1") (pinfunction "1_1") (pintype "passive"))
    )
    (net (code "19") (name "Net-(D10-C)") (class "Default")
      (node (ref "D10") (pin "1") (pinfunction "C_1") (pintype "passive"))
      (node (ref "R8") (pin "1") (pinfunction "1_1") (pintype "passive"))
    )
    (net (code "20") (name "Net-(P5-3.3V)") (class "Default")
      (node (ref "P5") (pin "P$3") (pinfunction "3.3V_P$3") (pintype "bidirectional"))
      (node (ref "Q5") (pin "3") (pinfunction "D_3") (pintype "passive"))
    )
    (net (code "21") (name "Net-(Q1-D)") (class "Default")
      (node (ref "P10") (pin "-") (pinfunction "-_-") (pintype "bidirectional"))
      (node (ref "Q1") (pin "3") (pinfunction "D_3") (pintype "passive"))
    )
    (net (code "22") (name "Net-(Q2-D)") (class "Default")
      (node (ref "P11") (pin "-") (pinfunction "-_-") (pintype "bidirectional"))
      (node (ref "Q2") (pin "3") (pinfunction "D_3") (pintype "passive"))
    )
    (net (code "23") (name "Net-(Q3-D)") (class "Default")
      (node (ref "P12") (pin "-") (pinfunction "-_-") (pintype "bidirectional"))
      (node (ref "Q3") (pin "3") (pinfunction "D_3") (pintype "passive"))
    )
    (net (code "24") (name "Net-(Q4-D)") (class "Default")
      (node (ref "P13") (pin "-") (pinfunction "-_-") (pintype "bidirectional"))
      (node (ref "Q4") (pin "3") (pinfunction "D_3") (pintype "passive"))
    )
    (net (code "25") (name "Net-(U$1-BOOT0)") (class "Default")
      (node (ref "R11") (pin "2") (pinfunction "2_2") (pintype "passive"))
      (node (ref "U$1") (pin "60") (pinfunction "BOOT0_60") (pintype "input"))
    )
    (net (code "26") (name "Net-(U$1-BOOT1(PB2))") (class "Default")
      (node (ref "R2") (pin "2") (pinfunction "2_2") (pintype "passive"))
      (node (ref "U$1") (pin "28") (pinfunction "BOOT1(PB2)_28") (pintype "input"))
    )
    (net (code "27") (name "Net-(U$1-NRST)") (class "Default")
      (node (ref "C25") (pin "1") (pinfunction "1_1") (pintype "passive"))
      (node (ref "U$1") (pin "7") (pinfunction "NRST_7") (pintype "input"))
      (node (ref "U$5") (pin "2") (pinfunction "P$2_2") (pintype "bidirectional"))
    )
    (net (code "28") (name "Net-(U$1-OSC_IN(PH0))") (class "Default")
      (node (ref "C8") (pin "2") (pinfunction "2_2") (pintype "passive"))
      (node (ref "U$1") (pin "5") (pinfunction "OSC_IN(PH0)_5") (pintype "bidirectional"))
      (node (ref "Y1") (pin "1") (pinfunction "1_1") (pintype "passive"))
    )
    (net (code "29") (name "Net-(U$1-OSC_OUT(PH1))") (class "Default")
      (node (ref "C9") (pin "2") (pinfunction "2_2") (pintype "passive"))
      (node (ref "U$1") (pin "6") (pinfunction "OSC_OUT(PH1)_6") (pintype "bidirectional"))
      (node (ref "Y1") (pin "3") (pinfunction "3_3") (pintype "passive"))
    )
    (net (code "30") (name "Net-(U$1-PA9)") (class "Default")
      (node (ref "R4") (pin "2") (pinfunction "2_2") (pintype "passive"))
      (node (ref "U$1") (pin "42") (pinfunction "PA9_42") (pintype "bidirectional"))
    )
    (net (code "31") (name "Net-(U$1-PB10)") (class "Default")
      (node (ref "C10") (pin "2") (pinfunction "2_2") (pintype "passive"))
      (node (ref "R5") (pin "1") (pinfunction "1_1") (pintype "passive"))
      (node (ref "U$1") (pin "29") (pinfunction "PB10_29") (pintype "bidirectional"))
    )
    (net (code "32") (name "Net-(U$1-PB11)") (class "Default")
      (node (ref "C11") (pin "2") (pinfunction "2_2") (pintype "passive"))
      (node (ref "R6") (pin "1") (pinfunction "1_1") (pintype "passive"))
      (node (ref "U$1") (pin "30") (pinfunction "PB11_30") (pintype "bidirectional"))
    )
    (net (code "33") (name "Net-(U$1-PC14)") (class "Default")
      (node (ref "R1") (pin "2") (pinfunction "2_2") (pintype "passive"))
      (node (ref "U$1") (pin "3") (pinfunction "PC14_3") (pintype "bidirectional"))
    )
    (net (code "34") (name "Net-(U$1-PC15)") (class "Default")
      (node (ref "R9") (pin "2") (pinfunction "2_2") (pintype "passive"))
      (node (ref "U$1") (pin "4") (pinfunction "PC15_4") (pintype "bidirectional"))
    )
    (net (code "35") (name "Net-(U$1-VCAP_1)") (class "Default")
      (node (ref "C7") (pin "2") (pinfunction "2_2") (pintype "passive"))
      (node (ref "U$1") (pin "31") (pinfunction "VCAP_1_31") (pintype "bidirectional"))
    )
    (net (code "36") (name "Net-(U$1-VCAP_2)") (class "Default")
      (node (ref "C6") (pin "2") (pinfunction "2_2") (pintype "passive"))
      (node (ref "U$1") (pin "47") (pinfunction "VCAP_2_47") (pintype "bidirectional"))
    )
    (net (code "37") (name "Net-(U$5-P$1)") (class "Default")
      (node (ref "R3") (pin "2") (pinfunction "2_2") (pintype "passive"))
      (node (ref "U$5") (pin "1") (pinfunction "P$1_1") (pintype "bidirectional"))
    )
    (net (code "38") (name "Net-(U$6-P$2)") (class "Default")
      (node (ref "R11") (pin "1") (pinfunction "1_1") (pintype "passive"))
      (node (ref "R12") (pin "2") (pinfunction "2_2") (pintype "passive"))
      (node (ref "U$6") (pin "2") (pinfunction "P$2_2") (pintype "bidirectional"))
    )
    (net (code "39") (name "Net-(U$8-1_L1)") (class "Default")
      (node (ref "U$8") (pin "P$1") (pinfunction "1_L1_P$1") (pintype "bidirectional"))
      (node (ref "U$9") (pin "P$1") (pinfunction "P$3_P$1") (pintype "bidirectional"))
    )
    (net (code "40") (name "Net-(U$8-6_VAUX)") (class "Default")
      (node (ref "C34") (pin "2") (pinfunction "2_2") (pintype "passive"))
      (node (ref "U$8") (pin "P$6") (pinfunction "6_VAUX_P$6") (pintype "bidirectional"))
    )
    (net (code "41") (name "Net-(U$8-8_FB)") (class "Default")
      (node (ref "C35") (pin "2") (pinfunction "2_2") (pintype "passive"))
      (node (ref "R15") (pin "2") (pinfunction "2_2") (pintype "passive"))
      (node (ref "R21") (pin "1") (pinfunction "1_1") (pintype "passive"))
      (node (ref "U$8") (pin "P$8") (pinfunction "8_FB_P$8") (pintype "bidirectional"))
    )
    (net (code "42") (name "Net-(U$8-10_L2)") (class "Default")
      (node (ref "U$8") (pin "P$10") (pinfunction "10_L2_P$10") (pintype "bidirectional"))
      (node (ref "U$9") (pin "P$2") (pinfunction "P$4_P$2") (pintype "bidirectional"))
    )
    (net (code "43") (name "Net-(U1-EN)") (class "Default")
      (node (ref "C28") (pin "1") (pinfunction "1_1") (pintype "passive"))
      (node (ref "R14") (pin "1") (pinfunction "1_1") (pintype "passive"))
      (node (ref "U1") (pin "4") (pinfunction "EN_4") (pintype "bidirectional"))
    )
    (net (code "44") (name "Net-(U1-FB)") (class "Default")
      (node (ref "R13") (pin "2") (pinfunction "2_2") (pintype "passive"))
      (node (ref "R7") (pin "2") (pinfunction "2_2") (pintype "passive"))
      (node (ref "U1") (pin "3") (pinfunction "FB_3") (pintype "bidirectional"))
    )
    (net (code "45") (name "PG") (class "Default")
      (node (ref "R23") (pin "2") (pinfunction "2_2") (pintype "passive"))
      (node (ref "U$8") (pin "P$5") (pinfunction "5_PG_P$5") (pintype "bidirectional"))
    )
    (net (code "46") (name "SDIO_CK") (class "Default")
      (node (ref "U$1") (pin "53") (pinfunction "PC12_53") (pintype "bidirectional"))
      (node (ref "U3") (pin "5") (pinfunction "SCK_5") (pintype "bidirectional"))
    )
    (net (code "47") (name "SDIO_CMD") (class "Default")
      (node (ref "U$1") (pin "54") (pinfunction "PD2_54") (pintype "bidirectional"))
      (node (ref "U3") (pin "3") (pinfunction "DI_3") (pintype "bidirectional"))
    )
    (net (code "48") (name "SDIO_D0") (class "Default")
      (node (ref "U$1") (pin "39") (pinfunction "PC8_39") (pintype "bidirectional"))
      (node (ref "U3") (pin "7") (pinfunction "DO_7") (pintype "bidirectional"))
    )
    (net (code "49") (name "SDIO_D1") (class "Default")
      (node (ref "U$1") (pin "40") (pinfunction "PC9_40") (pintype "bidirectional"))
      (node (ref "U3") (pin "8") (pinfunction "RSV_8") (pintype "bidirectional"))
    )
    (net (code "50") (name "SDIO_D2") (class "Default")
      (node (ref "U$1") (pin "51") (pinfunction "PC10_51") (pintype "bidirectional"))
      (node (ref "U3") (pin "1") (pinfunction "NC_1") (pintype "bidirectional"))
    )
    (net (code "51") (name "SDIO_D3") (class "Default")
      (node (ref "U$1") (pin "52") (pinfunction "PC11_52") (pintype "bidirectional"))
      (node (ref "U3") (pin "2") (pinfunction "CS_2") (pintype "bidirectional"))
    )
    (net (code "52") (name "SD_DETECT") (class "Default")
      (node (ref "U$1") (pin "50") (pinfunction "PA15_50") (pintype "bidirectional"))
      (node (ref "U3") (pin "CD1") (pinfunction "SHIELD_CD1") (pintype "bidirectional"))
    )
    (net (code "53") (name "SPI2_MISO") (class "Default")
      (node (ref "U$1") (pin "10") (pinfunction "PC2_10") (pintype "bidirectional"))
    )
    (net (code "54") (name "SPI2_MOSI") (class "Default")
      (node (ref "U$1") (pin "11") (pinfunction "PC3_11") (pintype "bidirectional"))
    )
    (net (code "55") (name "SW_RECEIVER") (class "Default")
      (node (ref "Q5") (pin "1") (pinfunction "G_1") (pintype "passive"))
      (node (ref "R22") (pin "2") (pinfunction "2_2") (pintype "passive"))
      (node (ref "U$1") (pin "20") (pinfunction "PA4_20") (pintype "bidirectional"))
    )
    (net (code "56") (name "TIM2_CH2") (class "Default")
      (node (ref "Q1") (pin "1") (pinfunction "G_1") (pintype "passive"))
      (node (ref "U$1") (pin "55") (pinfunction "PB3_55") (pintype "bidirectional"))
      (node (ref "U$11") (pin "P$2") (pinfunction "P$2_P$2") (pintype "bidirectional"))
    )
    (net (code "57") (name "TIM3_CH1") (class "Default")
      (node (ref "Q2") (pin "1") (pinfunction "G_1") (pintype "passive"))
      (node (ref "U$1") (pin "56") (pinfunction "PB4_56") (pintype "bidirectional"))
      (node (ref "U$11") (pin "P$3") (pinfunction "P$3_P$3") (pintype "bidirectional"))
    )
    (net (code "58") (name "TIM3_CH2") (class "Default")
      (node (ref "U$1") (pin "57") (pinfunction "PB5_57") (pintype "bidirectional"))
      (node (ref "U$11") (pin "P$4") (pinfunction "P$4_P$4") (pintype "bidirectional"))
    )
    (net (code "59") (name "TIM4_CH1") (class "Default")
      (node (ref "Q3") (pin "1") (pinfunction "G_1") (pintype "passive"))
      (node (ref "U$1") (pin "58") (pinfunction "PB6_58") (pintype "bidirectional"))
      (node (ref "U$11") (pin "P$5") (pinfunction "P$5_P$5") (pintype "bidirectional"))
    )
    (net (code "60") (name "TIM4_CH2") (class "Default")
      (node (ref "U$1") (pin "59") (pinfunction "PB7_59") (pintype "bidirectional"))
      (node (ref "U$11") (pin "P$6") (pinfunction "P$6_P$6") (pintype "bidirectional"))
    )
    (net (code "61") (name "TIM4_CH3") (class "Default")
      (node (ref "Q4") (pin "1") (pinfunction "G_1") (pintype "passive"))
      (node (ref "U$1") (pin "61") (pinfunction "PB8_61") (pintype "bidirectional"))
      (node (ref "U$11") (pin "P$7") (pinfunction "P$7_P$7") (pintype "bidirectional"))
    )
    (net (code "62") (name "UART4_RX") (class "Default")
      (node (ref "U$1") (pin "15") (pinfunction "PA1_15") (pintype "bidirectional"))
      (node (ref "U$10") (pin "P$2") (pinfunction "P$2_P$2") (pintype "bidirectional"))
    )
    (net (code "63") (name "UART4_TX") (class "Default")
      (node (ref "U$1") (pin "14") (pinfunction "PA0_14") (pintype "bidirectional"))
      (node (ref "U$10") (pin "P$1") (pinfunction "P$1_P$1") (pintype "bidirectional"))
    )
    (net (code "64") (name "USART2_RX") (class "Default")
      (node (ref "P5") (pin "P$1") (pinfunction "DATA_P$1") (pintype "bidirectional"))
      (node (ref "U$1") (pin "17") (pinfunction "PA3_17") (pintype "bidirectional"))
    )
    (net (code "65") (name "USART2_TX") (class "Default")
      (node (ref "U$1") (pin "16") (pinfunction "PA2_16") (pintype "bidirectional"))
    )
    (net (code "66") (name "USB_OTG_FS_DM") (class "Default")
      (node (ref "U$1") (pin "44") (pinfunction "PA11_44") (pintype "bidirectional"))
      (node (ref "U$2") (pin "2") (pinfunction "2_2") (pintype "passive"))
    )
    (net (code "67") (name "USB_OTG_FS_DP") (class "Default")
      (node (ref "U$1") (pin "45") (pinfunction "PA12_45") (pintype "bidirectional"))
      (node (ref "U$2") (pin "3") (pinfunction "3_3") (pintype "passive"))
    )
    (net (code "68") (name "USB_OTG_FS_ID") (class "Default")
      (node (ref "U$1") (pin "43") (pinfunction "PA10_43") (pintype "bidirectional"))
      (node (ref "U$2") (pin "4") (pinfunction "4_4") (pintype "passive"))
    )
    (net (code "69") (name "USB_OTG_VBUS") (class "Default")
      (node (ref "D10") (pin "2") (pinfunction "A_2") (pintype "passive"))
      (node (ref "R4") (pin "1") (pinfunction "1_1") (pintype "passive"))
      (node (ref "U$2") (pin "1") (pinfunction "1_1") (pintype "passive"))
    )
    (net (code "70") (name "VBAT") (class "Default")
      (node (ref "C31") (pin "2") (pinfunction "2_2") (pintype "passive"))
      (node (ref "C32") (pin "1") (pinfunction "1_1") (pintype "passive"))
      (node (ref "C33") (pin "1") (pinfunction "1_1") (pintype "passive"))
      (node (ref "C41") (pin "2") (pinfunction "2_2") (pintype "passive"))
      (node (ref "P10") (pin "+") (pinfunction "+_+") (pintype "bidirectional"))
      (node (ref "P11") (pin "+") (pinfunction "+_+") (pintype "bidirectional"))
      (node (ref "P12") (pin "+") (pinfunction "+_+") (pintype "bidirectional"))
      (node (ref "P13") (pin "+") (pinfunction "+_+") (pintype "bidirectional"))
      (node (ref "R14") (pin "2") (pinfunction "2_2") (pintype "passive"))
      (node (ref "R24") (pin "2") (pinfunction "2_2") (pintype "passive"))
      (node (ref "R8") (pin "2") (pinfunction "2_2") (pintype "passive"))
      (node (ref "U$8") (pin "P$2") (pinfunction "2_VIN_P$2") (pintype "bidirectional"))
      (node (ref "U$8") (pin "P$3") (pinfunction "3_EN_P$3") (pintype "bidirectional"))
      (node (ref "U1") (pin "5") (pinfunction "VIN_5") (pintype "bidirectional"))
      (node (ref "U4") (pin "1") (pinfunction "IN_1") (pintype "input"))
    )
    (net (code "71") (name "unconnected-(U$1-PA8-Pad41)") (class "Default")
      (node (ref "U$1") (pin "41") (pinfunction "PA8_41") (pintype "bidirectional"))
    )
    (net (code "72") (name "unconnected-(U$1-PA13-Pad46)") (class "Default")
      (node (ref "U$1") (pin "46") (pinfunction "PA13_46") (pintype "bidirectional"))
    )
    (net (code "73") (name "unconnected-(U$1-PA14-Pad49)") (class "Default")
      (node (ref "U$1") (pin "49") (pinfunction "PA14_49") (pintype "bidirectional"))
    )
    (net (code "74") (name "unconnected-(U$1-PB0-Pad26)") (class "Default")
      (node (ref "U$1") (pin "26") (pinfunction "PB0_26") (pintype "bidirectional"))
    )
    (net (code "75") (name "unconnected-(U$1-PB1-Pad27)") (class "Default")
      (node (ref "U$1") (pin "27") (pinfunction "PB1_27") (pintype "bidirectional"))
    )
    (net (code "76") (name "unconnected-(U$1-PB9-Pad62)") (class "Default")
      (node (ref "U$1") (pin "62") (pinfunction "PB9_62") (pintype "bidirectional"))
    )
    (net (code "77") (name "unconnected-(U$1-PB14-Pad35)") (class "Default")
      (node (ref "U$1") (pin "35") (pinfunction "PB14_35") (pintype "bidirectional"))
    )
    (net (code "78") (name "unconnected-(U$1-PB15-Pad36)") (class "Default")
      (node (ref "U$1") (pin "36") (pinfunction "PB15_36") (pintype "bidirectional"))
    )
    (net (code "79") (name "unconnected-(U$1-PC0-Pad8)") (class "Default")
      (node (ref "U$1") (pin "8") (pinfunction "PC0_8") (pintype "bidirectional"))
    )
    (net (code "80") (name "unconnected-(U$1-PC1-Pad9)") (class "Default")
      (node (ref "U$1") (pin "9") (pinfunction "PC1_9") (pintype "bidirectional"))
    )
    (net (code "81") (name "unconnected-(U$1-PC5-Pad25)") (class "Default")
      (node (ref "U$1") (pin "25") (pinfunction "PC5_25") (pintype "bidirectional"))
    )
    (net (code "82") (name "unconnected-(U$1-PC6-Pad37)") (class "Default")
      (node (ref "U$1") (pin "37") (pinfunction "PC6_37") (pintype "bidirectional"))
    )
    (net (code "83") (name "unconnected-(U$1-PC7-Pad38)") (class "Default")
      (node (ref "U$1") (pin "38") (pinfunction "PC7_38") (pintype "bidirectional"))
    )
    (net (code "84") (name "unconnected-(U$1-PC13-Pad2)") (class "Default")
      (node (ref "U$1") (pin "2") (pinfunction "PC13_2") (pintype "bidirectional"))
    )
    (net (code "85") (name "unconnected-(U$4-2_CSB-PadP$2)") (class "Default")
      (node (ref "U$4") (pin "P$2") (pinfunction "2_CSB_P$2") (pintype "bidirectional"))
    )
    (net (code "86") (name "unconnected-(U$4-5_SDO-PadP$5)") (class "Default")
      (node (ref "U$4") (pin "P$5") (pinfunction "5_SDO_P$5") (pintype "bidirectional"))
    )
    (net (code "87") (name "unconnected-(U2-AD0{slash}SDO-Pad9)") (class "Default")
      (node (ref "U2") (pin "9") (pinfunction "AD0/SDO_9") (pintype "bidirectional"))
    )
    (net (code "88") (name "unconnected-(U2-AUX_CLK-Pad7)") (class "Default")
      (node (ref "U2") (pin "7") (pinfunction "AUX_CLK_7") (pintype "open_collector"))
    )
    (net (code "89") (name "unconnected-(U2-AUX_DA-Pad21)") (class "Default")
      (node (ref "U2") (pin "21") (pinfunction "AUX_DA_21") (pintype "open_collector"))
    )
    (net (code "90") (name "unconnected-(U2-INT-Pad12)") (class "Default")
      (node (ref "U2") (pin "12") (pinfunction "INT_12") (pintype "open_collector"))
    )
    (net (code "91") (name "unconnected-(U2-NC1-Pad2)") (class "Default")
      (node (ref "U2") (pin "2") (pinfunction "NC1_2") (pintype "passive"))
    )
    (net (code "92") (name "unconnected-(U2-NC2-Pad3)") (class "Default")
      (node (ref "U2") (pin "3") (pinfunction "NC2_3") (pintype "passive"))
    )
    (net (code "93") (name "unconnected-(U2-NC3-Pad4)") (class "Default")
      (node (ref "U2") (pin "4") (pinfunction "NC3_4") (pintype "passive"))
    )
    (net (code "94") (name "unconnected-(U2-NC4-Pad5)") (class "Default")
      (node (ref "U2") (pin "5") (pinfunction "NC4_5") (pintype "passive"))
    )
    (net (code "95") (name "unconnected-(U2-NC5-Pad6)") (class "Default")
      (node (ref "U2") (pin "6") (pinfunction "NC5_6") (pintype "passive"))
    )
    (net (code "96") (name "unconnected-(U2-NC6-Pad14)") (class "Default")
      (node (ref "U2") (pin "14") (pinfunction "NC6_14") (pintype "passive"))
    )
    (net (code "97") (name "unconnected-(U2-NC7-Pad15)") (class "Default")
      (node (ref "U2") (pin "15") (pinfunction "NC7_15") (pintype "passive"))
    )
    (net (code "98") (name "unconnected-(U2-NC8-Pad16)") (class "Default")
      (node (ref "U2") (pin "16") (pinfunction "NC8_16") (pintype "passive"))
    )
    (net (code "99") (name "unconnected-(U2-NC9-Pad17)") (class "Default")
      (node (ref "U2") (pin "17") (pinfunction "NC9_17") (pintype "passive"))
    )
    (net (code "100") (name "unconnected-(U2-RESV-Pad19)") (class "Default")
      (node (ref "U2") (pin "19") (pinfunction "RESV_19") (pintype "passive"))
    )
    (net (code "101") (name "unconnected-(U4-ADJ-Pad4)") (class "Default")
      (node (ref "U4") (pin "4") (pinfunction "ADJ_4") (pintype "input"))
    )
  )
)
